# Atmega2560.net
KiCad netlist of a schematic drawn in EAGLE
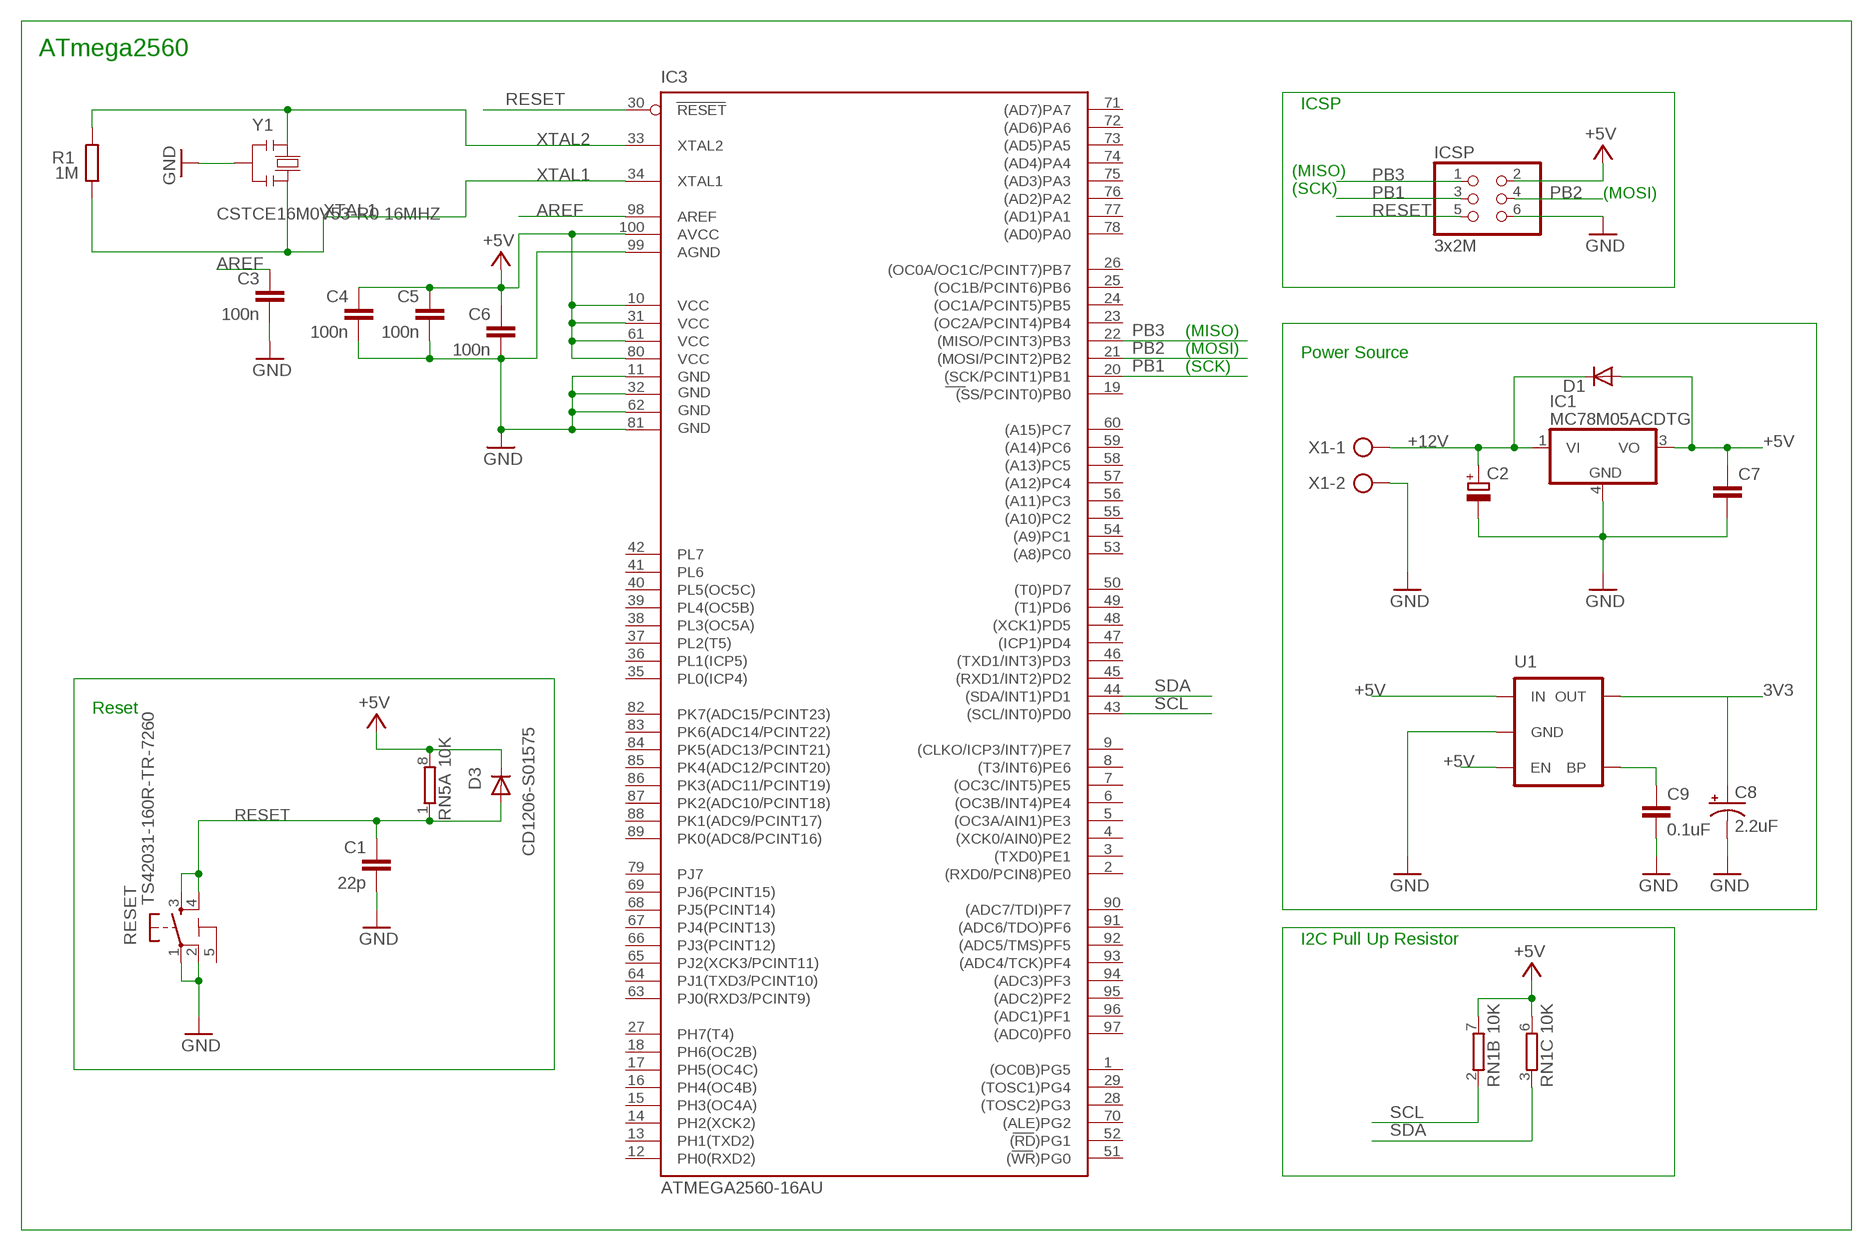
[diagram p0: schematic, sheet 1]

(export (version "E")
  (design (tool "Eeschema 10.0.6"))
  (components
    (comp (ref "C1")
      (value "22p")
      (footprint "eagle-import:C0603-ROUND")
      (libsource (lib "eagle-import") (part "C-EU0603-RND"))
    )
    (comp (ref "C2")
      (value "CPOL-EUE5-13")
      (footprint "eagle-import:E5-13")
      (libsource (lib "eagle-import") (part "CPOL-EUE5-13"))
    )
    (comp (ref "C3")
      (value "100n")
      (footprint "eagle-import:C0603-ROUND")
      (libsource (lib "eagle-import") (part "C-EU0603-RND"))
    )
    (comp (ref "C4")
      (value "100n")
      (footprint "eagle-import:C0603-ROUND")
      (libsource (lib "eagle-import") (part "C-EU0603-RND"))
    )
    (comp (ref "C5")
      (value "100n")
      (footprint "eagle-import:C0603-ROUND")
      (libsource (lib "eagle-import") (part "C-EU0603-RND"))
    )
    (comp (ref "C6")
      (value "100n")
      (footprint "eagle-import:C0603-ROUND")
      (libsource (lib "eagle-import") (part "C-EU0603-RND"))
    )
    (comp (ref "C7")
      (value "CAPPTH")
      (footprint "eagle-import:CAP-PTH-SMALL")
      (libsource (lib "eagle-import") (part "CAPPTH"))
    )
    (comp (ref "C8")
      (value "2.2uF")
      (footprint "eagle-import:EIA3216")
      (libsource (lib "eagle-import") (part "10UF-TANT"))
    )
    (comp (ref "C9")
      (value "0.1uF")
      (footprint "eagle-import:0402-CAP")
      (libsource (lib "eagle-import") (part "0.1UF-25V(+80/-20%)(0603)"))
    )
    (comp (ref "D1")
      (value "DIODESMA-KIT")
      (footprint "eagle-import:SMA-DIODE-KIT")
      (libsource (lib "eagle-import") (part "DIODESMA-KIT"))
    )
    (comp (ref "D3")
      (value "CD1206-S01575")
      (footprint "eagle-import:MINIMELF")
      (libsource (lib "eagle-import") (part "DIODE-MINIMELF"))
    )
    (comp (ref "IC1")
      (value "MC78M05ACDTG")
      (footprint "eagle-import:DPACK_3")
      (libsource (lib "eagle-import") (part "MC78M05ACDTG"))
    )
    (comp (ref "IC3")
      (value "ATMEGA2560-16AU")
      (footprint "eagle-import:TQFP100")
      (libsource (lib "eagle-import") (part "ATMEGA2560AU2560-16"))
    )
    (comp (ref "ICSP")
      (value "3x2M")
      (footprint "eagle-import:2X03")
      (libsource (lib "eagle-import") (part "PINHD-2X3"))
    )
    (comp (ref "R1")
      (value "1M")
      (footprint "eagle-import:R0603-ROUND")
      (libsource (lib "eagle-import") (part "R-EU_R0603"))
    )
    (comp (ref "RESET")
      (value "TS42031-160R-TR-7260")
      (footprint "eagle-import:TS42")
      (libsource (lib "eagle-import") (part "TS42"))
    )
    (comp (ref "RN1")
      (value "10K")
      (footprint "eagle-import:CAT16")
      (libsource (lib "eagle-import") (part "4R-NCAT16"))
    )
    (comp (ref "RN5")
      (value "10K")
      (footprint "eagle-import:CAT16")
      (libsource (lib "eagle-import") (part "4R-NCAT16"))
    )
    (comp (ref "U1")
      (value "MIC52053.3V")
      (footprint "eagle-import:SOT23-5")
      (libsource (lib "eagle-import") (part "MIC52053.3V"))
    )
    (comp (ref "X1")
      (value "AK500/2")
      (footprint "eagle-import:AK500_2")
      (libsource (lib "eagle-import") (part "AK500/2"))
    )
    (comp (ref "Y1")
      (value "CSTCE16M0V53-R0 16MHZ")
      (footprint "eagle-import:RESONATOR")
      (libsource (lib "eagle-import") (part "RESONATORMU"))
    )
  )
  (nets
    (net (code "1") (name "+5V") (class "Default")
      (node (ref "C4") (pin "1") (pinfunction "1_1") (pintype "passive"))
      (node (ref "C5") (pin "1") (pinfunction "1_1") (pintype "passive"))
      (node (ref "C6") (pin "1") (pinfunction "1_1") (pintype "passive"))
      (node (ref "C7") (pin "1") (pinfunction "1_1") (pintype "passive"))
      (node (ref "D1") (pin "A") (pinfunction "A_A") (pintype "passive"))
      (node (ref "D3") (pin "C") (pinfunction "C_C") (pintype "passive"))
      (node (ref "IC1") (pin "3") (pinfunction "VO_3") (pintype "passive"))
      (node (ref "IC3") (pin "10") (pinfunction "VCC_10") (pintype "power_in"))
      (node (ref "IC3") (pin "100") (pinfunction "AVCC_100") (pintype "power_in"))
      (node (ref "IC3") (pin "31") (pinfunction "VCC1_31") (pintype "power_in"))
      (node (ref "IC3") (pin "61") (pinfunction "VCC2_61") (pintype "power_in"))
      (node (ref "IC3") (pin "80") (pinfunction "VCC3_80") (pintype "power_in"))
      (node (ref "ICSP") (pin "2") (pinfunction "2_2") (pintype "passive"))
      (node (ref "RN1") (pin "6") (pinfunction "2_6") (pintype "passive"))
      (node (ref "RN1") (pin "7") (pinfunction "2_7") (pintype "passive"))
      (node (ref "RN5") (pin "8") (pinfunction "2_8") (pintype "passive"))
      (node (ref "U1") (pin "1") (pinfunction "IN_1") (pintype "input"))
      (node (ref "U1") (pin "3") (pinfunction "EN_3") (pintype "input"))
    )
    (net (code "2") (name "/+12V") (class "Default")
      (node (ref "C2") (pin "+") (pinfunction "+_+") (pintype "passive"))
      (node (ref "D1") (pin "C") (pinfunction "C_C") (pintype "passive"))
      (node (ref "IC1") (pin "1") (pinfunction "VI_1") (pintype "input"))
      (node (ref "X1") (pin "1") (pinfunction "KL_1") (pintype "passive"))
    )
    (net (code "3") (name "/3V3") (class "Default")
      (node (ref "C8") (pin "A") (pinfunction "+_A") (pintype "passive"))
      (node (ref "U1") (pin "5") (pinfunction "OUT_5") (pintype "passive"))
    )
    (net (code "4") (name "/5-GND") (class "Default")
      (node (ref "RESET") (pin "5") (pinfunction "5-GND_5") (pintype "power_in"))
    )
    (net (code "5") (name "/AREF") (class "Default")
      (node (ref "C3") (pin "1") (pinfunction "1_1") (pintype "passive"))
      (node (ref "IC3") (pin "98") (pinfunction "AREF_98") (pintype "bidirectional"))
    )
    (net (code "6") (name "/PB1") (class "Default")
      (node (ref "IC3") (pin "20") (pinfunction "(SCK/PCINT1)PB1_20") (pintype "bidirectional"))
      (node (ref "ICSP") (pin "3") (pinfunction "3_3") (pintype "passive"))
    )
    (net (code "7") (name "/PB2") (class "Default")
      (node (ref "IC3") (pin "21") (pinfunction "(MOSI/PCINT2)PB2_21") (pintype "bidirectional"))
      (node (ref "ICSP") (pin "4") (pinfunction "4_4") (pintype "passive"))
    )
    (net (code "8") (name "/PB3") (class "Default")
      (node (ref "IC3") (pin "22") (pinfunction "(MISO/PCINT3)PB3_22") (pintype "bidirectional"))
      (node (ref "ICSP") (pin "1") (pinfunction "1_1") (pintype "passive"))
    )
    (net (code "9") (name "/RESET") (class "Default")
      (node (ref "C1") (pin "1") (pinfunction "1_1") (pintype "passive"))
      (node (ref "D3") (pin "A") (pinfunction "A_A") (pintype "passive"))
      (node (ref "IC3") (pin "30") (pinfunction "RESET_30") (pintype "input"))
      (node (ref "ICSP") (pin "5") (pinfunction "5_5") (pintype "passive"))
      (node (ref "RESET") (pin "3") (pinfunction "3_3") (pintype "passive"))
      (node (ref "RESET") (pin "4") (pinfunction "4_4") (pintype "passive"))
      (node (ref "RN5") (pin "1") (pinfunction "1_1") (pintype "passive"))
    )
    (net (code "10") (name "/SCL") (class "Default")
      (node (ref "IC3") (pin "43") (pinfunction "(SCL/INT0)PD0_43") (pintype "bidirectional"))
      (node (ref "RN1") (pin "2") (pinfunction "1_2") (pintype "passive"))
    )
    (net (code "11") (name "/SDA") (class "Default")
      (node (ref "IC3") (pin "44") (pinfunction "(SDA/INT1)PD1_44") (pintype "bidirectional"))
      (node (ref "RN1") (pin "3") (pinfunction "1_3") (pintype "passive"))
    )
    (net (code "12") (name "/XTAL1") (class "Default")
      (node (ref "IC3") (pin "34") (pinfunction "XTAL1_34") (pintype "input"))
      (node (ref "R1") (pin "1") (pinfunction "1_1") (pintype "passive"))
      (node (ref "Y1") (pin "3") (pinfunction "3_3") (pintype "passive"))
    )
    (net (code "13") (name "/XTAL2") (class "Default")
      (node (ref "IC3") (pin "33") (pinfunction "XTAL2_33") (pintype "output"))
      (node (ref "R1") (pin "2") (pinfunction "2_2") (pintype "passive"))
      (node (ref "Y1") (pin "1") (pinfunction "1_1") (pintype "passive"))
    )
    (net (code "14") (name "GND") (class "Default")
      (node (ref "C1") (pin "2") (pinfunction "2_2") (pintype "passive"))
      (node (ref "C2") (pin "-") (pinfunction "-_-") (pintype "passive"))
      (node (ref "C3") (pin "2") (pinfunction "2_2") (pintype "passive"))
      (node (ref "C4") (pin "2") (pinfunction "2_2") (pintype "passive"))
      (node (ref "C5") (pin "2") (pinfunction "2_2") (pintype "passive"))
      (node (ref "C6") (pin "2") (pinfunction "2_2") (pintype "passive"))
      (node (ref "C7") (pin "2") (pinfunction "2_2") (pintype "passive"))
      (node (ref "C8") (pin "C") (pinfunction "-_C") (pintype "passive"))
      (node (ref "C9") (pin "2") (pinfunction "2_2") (pintype "passive"))
      (node (ref "IC1") (pin "4") (pinfunction "GND_4") (pintype "passive"))
      (node (ref "IC3") (pin "11") (pinfunction "GND_11") (pintype "power_in"))
      (node (ref "IC3") (pin "32") (pinfunction "GND1_32") (pintype "power_in"))
      (node (ref "IC3") (pin "62") (pinfunction "GND2_62") (pintype "power_in"))
      (node (ref "IC3") (pin "81") (pinfunction "GND3_81") (pintype "power_in"))
      (node (ref "IC3") (pin "99") (pinfunction "AGND_99") (pintype "power_in"))
      (node (ref "ICSP") (pin "6") (pinfunction "6_6") (pintype "passive"))
      (node (ref "RESET") (pin "1") (pinfunction "1_1") (pintype "passive"))
      (node (ref "RESET") (pin "2") (pinfunction "2_2") (pintype "passive"))
      (node (ref "U1") (pin "2") (pinfunction "GND_2") (pintype "input"))
      (node (ref "X1") (pin "2") (pinfunction "KL_2") (pintype "passive"))
      (node (ref "Y1") (pin "2") (pinfunction "2_2") (pintype "passive"))
    )
    (net (code "15") (name "Net-(U1-BP)") (class "Default")
      (node (ref "C9") (pin "1") (pinfunction "1_1") (pintype "passive"))
      (node (ref "U1") (pin "4") (pinfunction "BP_4") (pintype "input"))
    )
    (net (code "16") (name "unconnected-(IC3-(A8)PC0-Pad53)") (class "Default")
      (node (ref "IC3") (pin "53") (pinfunction "(A8)PC0_53") (pintype "bidirectional"))
    )
    (net (code "17") (name "unconnected-(IC3-(A9)PC1-Pad54)") (class "Default")
      (node (ref "IC3") (pin "54") (pinfunction "(A9)PC1_54") (pintype "bidirectional"))
    )
    (net (code "18") (name "unconnected-(IC3-(A10)PC2-Pad55)") (class "Default")
      (node (ref "IC3") (pin "55") (pinfunction "(A10)PC2_55") (pintype "bidirectional"))
    )
    (net (code "19") (name "unconnected-(IC3-(A11)PC3-Pad56)") (class "Default")
      (node (ref "IC3") (pin "56") (pinfunction "(A11)PC3_56") (pintype "bidirectional"))
    )
    (net (code "20") (name "unconnected-(IC3-(A12)PC4-Pad57)") (class "Default")
      (node (ref "IC3") (pin "57") (pinfunction "(A12)PC4_57") (pintype "bidirectional"))
    )
    (net (code "21") (name "unconnected-(IC3-(A13)PC5-Pad58)") (class "Default")
      (node (ref "IC3") (pin "58") (pinfunction "(A13)PC5_58") (pintype "bidirectional"))
    )
    (net (code "22") (name "unconnected-(IC3-(A14)PC6-Pad59)") (class "Default")
      (node (ref "IC3") (pin "59") (pinfunction "(A14)PC6_59") (pintype "bidirectional"))
    )
    (net (code "23") (name "unconnected-(IC3-(A15)PC7-Pad60)") (class "Default")
      (node (ref "IC3") (pin "60") (pinfunction "(A15)PC7_60") (pintype "bidirectional"))
    )
    (net (code "24") (name "unconnected-(IC3-(AD0)PA0-Pad78)") (class "Default")
      (node (ref "IC3") (pin "78") (pinfunction "(AD0)PA0_78") (pintype "bidirectional"))
    )
    (net (code "25") (name "unconnected-(IC3-(AD1)PA1-Pad77)") (class "Default")
      (node (ref "IC3") (pin "77") (pinfunction "(AD1)PA1_77") (pintype "bidirectional"))
    )
    (net (code "26") (name "unconnected-(IC3-(AD2)PA2-Pad76)") (class "Default")
      (node (ref "IC3") (pin "76") (pinfunction "(AD2)PA2_76") (pintype "bidirectional"))
    )
    (net (code "27") (name "unconnected-(IC3-(AD3)PA3-Pad75)") (class "Default")
      (node (ref "IC3") (pin "75") (pinfunction "(AD3)PA3_75") (pintype "bidirectional"))
    )
    (net (code "28") (name "unconnected-(IC3-(AD4)PA4-Pad74)") (class "Default")
      (node (ref "IC3") (pin "74") (pinfunction "(AD4)PA4_74") (pintype "bidirectional"))
    )
    (net (code "29") (name "unconnected-(IC3-(AD5)PA5-Pad73)") (class "Default")
      (node (ref "IC3") (pin "73") (pinfunction "(AD5)PA5_73") (pintype "bidirectional"))
    )
    (net (code "30") (name "unconnected-(IC3-(AD6)PA6-Pad72)") (class "Default")
      (node (ref "IC3") (pin "72") (pinfunction "(AD6)PA6_72") (pintype "bidirectional"))
    )
    (net (code "31") (name "unconnected-(IC3-(AD7)PA7-Pad71)") (class "Default")
      (node (ref "IC3") (pin "71") (pinfunction "(AD7)PA7_71") (pintype "bidirectional"))
    )
    (net (code "32") (name "unconnected-(IC3-(ADC0)PF0-Pad97)") (class "Default")
      (node (ref "IC3") (pin "97") (pinfunction "(ADC0)PF0_97") (pintype "bidirectional"))
    )
    (net (code "33") (name "unconnected-(IC3-(ADC1)PF1-Pad96)") (class "Default")
      (node (ref "IC3") (pin "96") (pinfunction "(ADC1)PF1_96") (pintype "bidirectional"))
    )
    (net (code "34") (name "unconnected-(IC3-(ADC2)PF2-Pad95)") (class "Default")
      (node (ref "IC3") (pin "95") (pinfunction "(ADC2)PF2_95") (pintype "bidirectional"))
    )
    (net (code "35") (name "unconnected-(IC3-(ADC3)PF3-Pad94)") (class "Default")
      (node (ref "IC3") (pin "94") (pinfunction "(ADC3)PF3_94") (pintype "bidirectional"))
    )
    (net (code "36") (name "unconnected-(IC3-(ADC4{slash}TCK)PF4-Pad93)") (class "Default")
      (node (ref "IC3") (pin "93") (pinfunction "(ADC4/TCK)PF4_93") (pintype "bidirectional"))
    )
    (net (code "37") (name "unconnected-(IC3-(ADC5{slash}TMS)PF5-Pad92)") (class "Default")
      (node (ref "IC3") (pin "92") (pinfunction "(ADC5/TMS)PF5_92") (pintype "bidirectional"))
    )
    (net (code "38") (name "unconnected-(IC3-(ADC6{slash}TDO)PF6-Pad91)") (class "Default")
      (node (ref "IC3") (pin "91") (pinfunction "(ADC6/TDO)PF6_91") (pintype "bidirectional"))
    )
    (net (code "39") (name "unconnected-(IC3-(ADC7{slash}TDI)PF7-Pad90)") (class "Default")
      (node (ref "IC3") (pin "90") (pinfunction "(ADC7/TDI)PF7_90") (pintype "bidirectional"))
    )
    (net (code "40") (name "unconnected-(IC3-(ALE)PG2-Pad70)") (class "Default")
      (node (ref "IC3") (pin "70") (pinfunction "(ALE)PG2_70") (pintype "bidirectional"))
    )
    (net (code "41") (name "unconnected-(IC3-(CLKO{slash}ICP3{slash}INT7)PE7-Pad9)") (class "Default")
      (node (ref "IC3") (pin "9") (pinfunction "(CLKO/ICP3/INT7)PE7_9") (pintype "bidirectional"))
    )
    (net (code "42") (name "unconnected-(IC3-(ICP1)PD4-Pad47)") (class "Default")
      (node (ref "IC3") (pin "47") (pinfunction "(ICP1)PD4_47") (pintype "bidirectional"))
    )
    (net (code "43") (name "unconnected-(IC3-(OC0A{slash}OC1C{slash}PCINT7)PB7-Pad26)") (class "Default")
      (node (ref "IC3") (pin "26") (pinfunction "(OC0A/OC1C/PCINT7)PB7_26") (pintype "bidirectional"))
    )
    (net (code "44") (name "unconnected-(IC3-(OC0B)PG5-Pad1)") (class "Default")
      (node (ref "IC3") (pin "1") (pinfunction "(OC0B)PG5_1") (pintype "bidirectional"))
    )
    (net (code "45") (name "unconnected-(IC3-(OC1A{slash}PCINT5)PB5-Pad24)") (class "Default")
      (node (ref "IC3") (pin "24") (pinfunction "(OC1A/PCINT5)PB5_24") (pintype "bidirectional"))
    )
    (net (code "46") (name "unconnected-(IC3-(OC1B{slash}PCINT6)PB6-Pad25)") (class "Default")
      (node (ref "IC3") (pin "25") (pinfunction "(OC1B/PCINT6)PB6_25") (pintype "bidirectional"))
    )
    (net (code "47") (name "unconnected-(IC3-(OC2A{slash}PCINT4)PB4-Pad23)") (class "Default")
      (node (ref "IC3") (pin "23") (pinfunction "(OC2A/PCINT4)PB4_23") (pintype "bidirectional"))
    )
    (net (code "48") (name "unconnected-(IC3-(OC3A{slash}AIN1)PE3-Pad5)") (class "Default")
      (node (ref "IC3") (pin "5") (pinfunction "(OC3A/AIN1)PE3_5") (pintype "bidirectional"))
    )
    (net (code "49") (name "unconnected-(IC3-(OC3B{slash}INT4)PE4-Pad6)") (class "Default")
      (node (ref "IC3") (pin "6") (pinfunction "(OC3B/INT4)PE4_6") (pintype "bidirectional"))
    )
    (net (code "50") (name "unconnected-(IC3-(OC3C{slash}INT5)PE5-Pad7)") (class "Default")
      (node (ref "IC3") (pin "7") (pinfunction "(OC3C/INT5)PE5_7") (pintype "bidirectional"))
    )
    (net (code "51") (name "unconnected-(IC3-(RD)PG1-Pad52)") (class "Default")
      (node (ref "IC3") (pin "52") (pinfunction "(RD)PG1_52") (pintype "bidirectional"))
    )
    (net (code "52") (name "unconnected-(IC3-(RXD0{slash}PCIN8)PE0-Pad2)") (class "Default")
      (node (ref "IC3") (pin "2") (pinfunction "(RXD0/PCIN8)PE0_2") (pintype "bidirectional"))
    )
    (net (code "53") (name "unconnected-(IC3-(RXD1{slash}INT2)PD2-Pad45)") (class "Default")
      (node (ref "IC3") (pin "45") (pinfunction "(RXD1/INT2)PD2_45") (pintype "bidirectional"))
    )
    (net (code "54") (name "unconnected-(IC3-(SS{slash}PCINT0)PB0-Pad19)") (class "Default")
      (node (ref "IC3") (pin "19") (pinfunction "(SS/PCINT0)PB0_19") (pintype "bidirectional"))
    )
    (net (code "55") (name "unconnected-(IC3-(T0)PD7-Pad50)") (class "Default")
      (node (ref "IC3") (pin "50") (pinfunction "(T0)PD7_50") (pintype "bidirectional"))
    )
    (net (code "56") (name "unconnected-(IC3-(T1)PD6-Pad49)") (class "Default")
      (node (ref "IC3") (pin "49") (pinfunction "(T1)PD6_49") (pintype "bidirectional"))
    )
    (net (code "57") (name "unconnected-(IC3-(T3{slash}INT6)PE6-Pad8)") (class "Default")
      (node (ref "IC3") (pin "8") (pinfunction "(T3/INT6)PE6_8") (pintype "bidirectional"))
    )
    (net (code "58") (name "unconnected-(IC3-(TOSC1)PG4-Pad29)") (class "Default")
      (node (ref "IC3") (pin "29") (pinfunction "(TOSC1)PG4_29") (pintype "bidirectional"))
    )
    (net (code "59") (name "unconnected-(IC3-(TOSC2)PG3-Pad28)") (class "Default")
      (node (ref "IC3") (pin "28") (pinfunction "(TOSC2)PG3_28") (pintype "bidirectional"))
    )
    (net (code "60") (name "unconnected-(IC3-(TXD0)PE1-Pad3)") (class "Default")
      (node (ref "IC3") (pin "3") (pinfunction "(TXD0)PE1_3") (pintype "bidirectional"))
    )
    (net (code "61") (name "unconnected-(IC3-(TXD1{slash}INT3)PD3-Pad46)") (class "Default")
      (node (ref "IC3") (pin "46") (pinfunction "(TXD1/INT3)PD3_46") (pintype "bidirectional"))
    )
    (net (code "62") (name "unconnected-(IC3-(WR)PG0-Pad51)") (class "Default")
      (node (ref "IC3") (pin "51") (pinfunction "(WR)PG0_51") (pintype "bidirectional"))
    )
    (net (code "63") (name "unconnected-(IC3-(XCK0{slash}AIN0)PE2-Pad4)") (class "Default")
      (node (ref "IC3") (pin "4") (pinfunction "(XCK0/AIN0)PE2_4") (pintype "bidirectional"))
    )
    (net (code "64") (name "unconnected-(IC3-(XCK1)PD5-Pad48)") (class "Default")
      (node (ref "IC3") (pin "48") (pinfunction "(XCK1)PD5_48") (pintype "bidirectional"))
    )
    (net (code "65") (name "unconnected-(IC3-PH0(RXD2)-Pad12)") (class "Default")
      (node (ref "IC3") (pin "12") (pinfunction "PH0(RXD2)_12") (pintype "bidirectional"))
    )
    (net (code "66") (name "unconnected-(IC3-PH1(TXD2)-Pad13)") (class "Default")
      (node (ref "IC3") (pin "13") (pinfunction "PH1(TXD2)_13") (pintype "bidirectional"))
    )
    (net (code "67") (name "unconnected-(IC3-PH2(XCK2)-Pad14)") (class "Default")
      (node (ref "IC3") (pin "14") (pinfunction "PH2(XCK2)_14") (pintype "bidirectional"))
    )
    (net (code "68") (name "unconnected-(IC3-PH3(OC4A)-Pad15)") (class "Default")
      (node (ref "IC3") (pin "15") (pinfunction "PH3(OC4A)_15") (pintype "bidirectional"))
    )
    (net (code "69") (name "unconnected-(IC3-PH4(OC4B)-Pad16)") (class "Default")
      (node (ref "IC3") (pin "16") (pinfunction "PH4(OC4B)_16") (pintype "bidirectional"))
    )
    (net (code "70") (name "unconnected-(IC3-PH5(OC4C)-Pad17)") (class "Default")
      (node (ref "IC3") (pin "17") (pinfunction "PH5(OC4C)_17") (pintype "bidirectional"))
    )
    (net (code "71") (name "unconnected-(IC3-PH6(OC2B)-Pad18)") (class "Default")
      (node (ref "IC3") (pin "18") (pinfunction "PH6(OC2B)_18") (pintype "bidirectional"))
    )
    (net (code "72") (name "unconnected-(IC3-PH7(T4)-Pad27)") (class "Default")
      (node (ref "IC3") (pin "27") (pinfunction "PH7(T4)_27") (pintype "bidirectional"))
    )
    (net (code "73") (name "unconnected-(IC3-PJ0(RXD3{slash}PCINT9)-Pad63)") (class "Default")
      (node (ref "IC3") (pin "63") (pinfunction "PJ0(RXD3/PCINT9)_63") (pintype "bidirectional"))
    )
    (net (code "74") (name "unconnected-(IC3-PJ1(TXD3{slash}PCINT10)-Pad64)") (class "Default")
      (node (ref "IC3") (pin "64") (pinfunction "PJ1(TXD3/PCINT10)_64") (pintype "bidirectional"))
    )
    (net (code "75") (name "unconnected-(IC3-PJ2(XCK3{slash}PCINT11)-Pad65)") (class "Default")
      (node (ref "IC3") (pin "65") (pinfunction "PJ2(XCK3/PCINT11)_65") (pintype "bidirectional"))
    )
    (net (code "76") (name "unconnected-(IC3-PJ3(PCINT12)-Pad66)") (class "Default")
      (node (ref "IC3") (pin "66") (pinfunction "PJ3(PCINT12)_66") (pintype "bidirectional"))
    )
    (net (code "77") (name "unconnected-(IC3-PJ4(PCINT13)-Pad67)") (class "Default")
      (node (ref "IC3") (pin "67") (pinfunction "PJ4(PCINT13)_67") (pintype "bidirectional"))
    )
    (net (code "78") (name "unconnected-(IC3-PJ5(PCINT14)-Pad68)") (class "Default")
      (node (ref "IC3") (pin "68") (pinfunction "PJ5(PCINT14)_68") (pintype "bidirectional"))
    )
    (net (code "79") (name "unconnected-(IC3-PJ6(PCINT15)-Pad69)") (class "Default")
      (node (ref "IC3") (pin "69") (pinfunction "PJ6(PCINT15)_69") (pintype "bidirectional"))
    )
    (net (code "80") (name "unconnected-(IC3-PJ7-Pad79)") (class "Default")
      (node (ref "IC3") (pin "79") (pinfunction "PJ7_79") (pintype "bidirectional"))
    )
    (net (code "81") (name "unconnected-(IC3-PK0(ADC8{slash}PCINT16)-Pad89)") (class "Default")
      (node (ref "IC3") (pin "89") (pinfunction "PK0(ADC8/PCINT16)_89") (pintype "bidirectional"))
    )
    (net (code "82") (name "unconnected-(IC3-PK1(ADC9{slash}PCINT17)-Pad88)") (class "Default")
      (node (ref "IC3") (pin "88") (pinfunction "PK1(ADC9/PCINT17)_88") (pintype "bidirectional"))
    )
    (net (code "83") (name "unconnected-(IC3-PK2(ADC10{slash}PCINT18)-Pad87)") (class "Default")
      (node (ref "IC3") (pin "87") (pinfunction "PK2(ADC10/PCINT18)_87") (pintype "bidirectional"))
    )
    (net (code "84") (name "unconnected-(IC3-PK3(ADC11{slash}PCINT19)-Pad86)") (class "Default")
      (node (ref "IC3") (pin "86") (pinfunction "PK3(ADC11/PCINT19)_86") (pintype "bidirectional"))
    )
    (net (code "85") (name "unconnected-(IC3-PK4(ADC12{slash}PCINT20)-Pad85)") (class "Default")
      (node (ref "IC3") (pin "85") (pinfunction "PK4(ADC12/PCINT20)_85") (pintype "bidirectional"))
    )
    (net (code "86") (name "unconnected-(IC3-PK5(ADC13{slash}PCINT21)-Pad84)") (class "Default")
      (node (ref "IC3") (pin "84") (pinfunction "PK5(ADC13/PCINT21)_84") (pintype "bidirectional"))
    )
    (net (code "87") (name "unconnected-(IC3-PK6(ADC14{slash}PCINT22)-Pad83)") (class "Default")
      (node (ref "IC3") (pin "83") (pinfunction "PK6(ADC14/PCINT22)_83") (pintype "bidirectional"))
    )
    (net (code "88") (name "unconnected-(IC3-PK7(ADC15{slash}PCINT23)-Pad82)") (class "Default")
      (node (ref "IC3") (pin "82") (pinfunction "PK7(ADC15/PCINT23)_82") (pintype "bidirectional"))
    )
    (net (code "89") (name "unconnected-(IC3-PL0(ICP4)-Pad35)") (class "Default")
      (node (ref "IC3") (pin "35") (pinfunction "PL0(ICP4)_35") (pintype "bidirectional"))
    )
    (net (code "90") (name "unconnected-(IC3-PL1(ICP5)-Pad36)") (class "Default")
      (node (ref "IC3") (pin "36") (pinfunction "PL1(ICP5)_36") (pintype "bidirectional"))
    )
    (net (code "91") (name "unconnected-(IC3-PL2(T5)-Pad37)") (class "Default")
      (node (ref "IC3") (pin "37") (pinfunction "PL2(T5)_37") (pintype "bidirectional"))
    )
    (net (code "92") (name "unconnected-(IC3-PL3(OC5A)-Pad38)") (class "Default")
      (node (ref "IC3") (pin "38") (pinfunction "PL3(OC5A)_38") (pintype "bidirectional"))
    )
    (net (code "93") (name "unconnected-(IC3-PL4(OC5B)-Pad39)") (class "Default")
      (node (ref "IC3") (pin "39") (pinfunction "PL4(OC5B)_39") (pintype "bidirectional"))
    )
    (net (code "94") (name "unconnected-(IC3-PL5(OC5C)-Pad40)") (class "Default")
      (node (ref "IC3") (pin "40") (pinfunction "PL5(OC5C)_40") (pintype "bidirectional"))
    )
    (net (code "95") (name "unconnected-(IC3-PL6-Pad41)") (class "Default")
      (node (ref "IC3") (pin "41") (pinfunction "PL6_41") (pintype "bidirectional"))
    )
    (net (code "96") (name "unconnected-(IC3-PL7-Pad42)") (class "Default")
      (node (ref "IC3") (pin "42") (pinfunction "PL7_42") (pintype "bidirectional"))
    )
  )
)
